# jackBus.net
KiCad netlist of a schematic drawn in Altium Designer
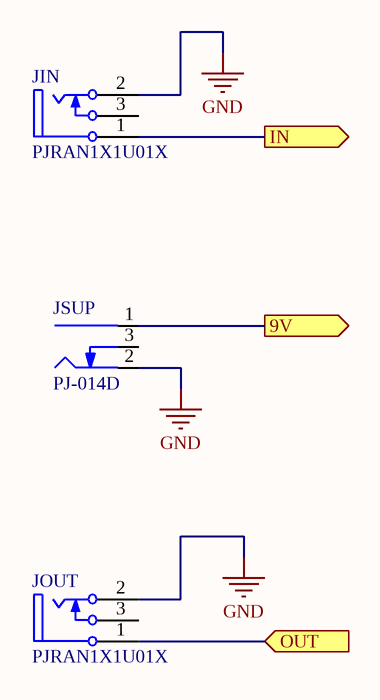
[diagram p0: jackBus.SchDoc]

(export (version "E")
  (design (tool "Eeschema 10.0.6"))
  (components
    (comp (ref "JIN")
      (value "PJRAN1X1U01X")
      (footprint "SWIT-PJRAN1X1U01X_V")
      (description "Female Phono Jack, 3 Position, Height 13 mm, Tail Length 4 mm, RoHS, Bulk")
      (fields (field (name "TOLERANCE") "10%"))
      (libsource (lib "p2 jack") (part "CMP-1772-00003-1"))
    )
    (comp (ref "JOUT")
      (value "PJRAN1X1U01X")
      (footprint "SWIT-PJRAN1X1U01X_V")
      (description "Female Phono Jack, 3 Position, Height 13 mm, Tail Length 4 mm, RoHS, Bulk")
      (fields (field (name "TOLERANCE") "10%"))
      (libsource (lib "p2 jack") (part "CMP-1772-00003-1"))
    )
    (comp (ref "JSUP")
      (value "PJ-014D")
      (footprint "CUI PJ-014D")
      (description "CONN PWR JACK 1.3X3.4MM SOLDER")
      (fields (field (name "MANUFACTURER") "CUI Devices"))
      (libsource (lib "Celestial Altium Library - altium_library") (part "Barrel Connector"))
    )
  )
  (nets
    (net (code "1") (name "/9V") (class "Default")
      (node (ref "JSUP") (pin "1") (pinfunction "Centre_1") (pintype "passive"))
    )
    (net (code "2") (name "/IN") (class "Default")
      (node (ref "JIN") (pin "1") (pinfunction "SLEEVE_1") (pintype "passive"))
    )
    (net (code "3") (name "/OUT") (class "Default")
      (node (ref "JOUT") (pin "1") (pinfunction "SLEEVE_1") (pintype "passive"))
    )
    (net (code "4") (name "GND") (class "Default")
      (node (ref "JIN") (pin "2") (pinfunction "TIP_2") (pintype "passive"))
      (node (ref "JOUT") (pin "2") (pinfunction "TIP_2") (pintype "passive"))
      (node (ref "JSUP") (pin "2") (pinfunction "Outer_2") (pintype "passive"))
    )
    (net (code "5") (name "unconnected-(JIN-SHUNT-Pad3)") (class "Default")
      (node (ref "JIN") (pin "3") (pinfunction "SHUNT_3") (pintype "passive"))
    )
    (net (code "6") (name "unconnected-(JOUT-SHUNT-Pad3)") (class "Default")
      (node (ref "JOUT") (pin "3") (pinfunction "SHUNT_3") (pintype "passive"))
    )
    (net (code "7") (name "unconnected-(JSUP-SW-Pad3)") (class "Default")
      (node (ref "JSUP") (pin "3") (pinfunction "SW_3") (pintype "passive"))
    )
  )
)
